# Avometer_v1_0.net
KiCad netlist of a schematic drawn in Altium Designer
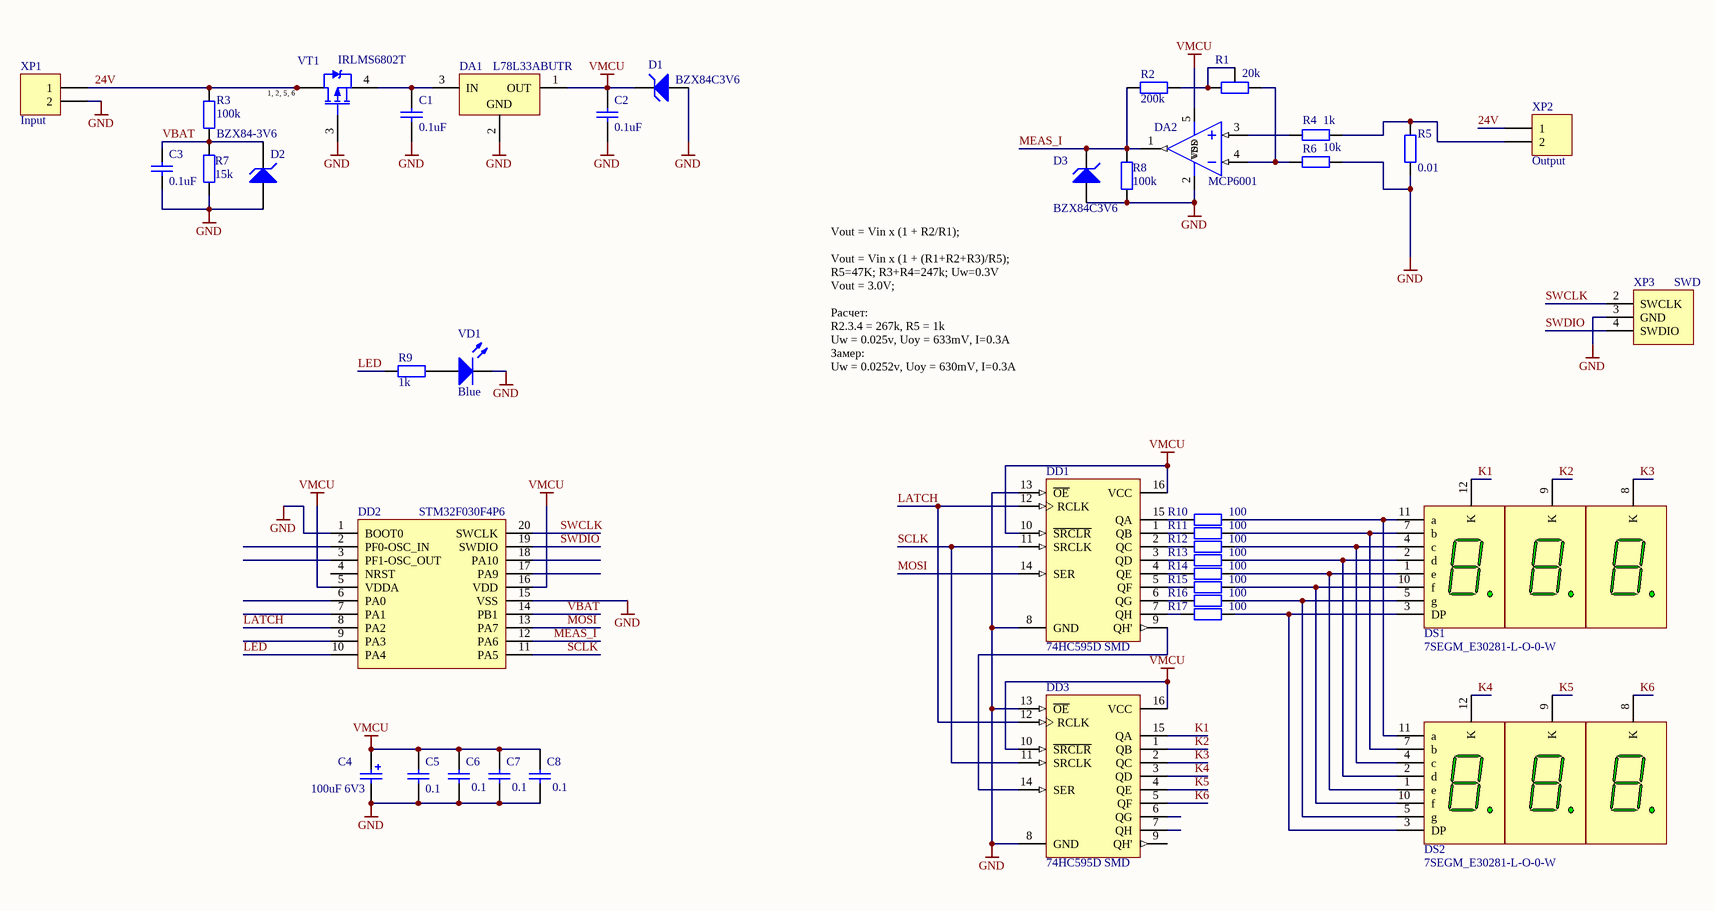
[diagram p0: Avometer v1.0.SchDoc]

(export (version "E")
  (design (tool "Eeschema 10.0.6"))
  (components
    (comp (ref "C1")
      (value "0.1uF")
      (footprint "CAP 0603_N")
      (description "Capacitor SMD")
      (libsource (lib "MyLibrary") (part "CAP_SMD"))
    )
    (comp (ref "C2")
      (value "0.1uF")
      (footprint "CAP 0603_N")
      (description "Capacitor SMD")
      (libsource (lib "MyLibrary") (part "CAP_SMD"))
    )
    (comp (ref "C3") (value "0.1uF") (footprint "CAP 0603_N") (libsource (lib "") (part "CAP_SMD_1")))
    (comp (ref "C4")
      (value "100uF 6V3")
      (footprint "CAP_TANT_B_TYPE_3528-21")
      (description "Capacitor SMD Tantalum")
      (libsource (lib "MyLibrary") (part "CAP_SMD_TANT"))
    )
    (comp (ref "C5")
      (value "0.1")
      (footprint "CAP 0603_N")
      (description "Capacitor SMD")
      (libsource (lib "MyLibrary") (part "CAP_SMD"))
    )
    (comp (ref "C6")
      (value "0.1")
      (footprint "CAP 0603_N")
      (description "Capacitor SMD")
      (libsource (lib "MyLibrary") (part "CAP_SMD"))
    )
    (comp (ref "C7")
      (value "0.1")
      (footprint "CAP 0603_N")
      (description "Capacitor SMD")
      (libsource (lib "MyLibrary") (part "CAP_SMD"))
    )
    (comp (ref "C8")
      (value "0.1")
      (footprint "CAP 0603_N")
      (description "Capacitor SMD")
      (libsource (lib "MyLibrary") (part "CAP_SMD"))
    )
    (comp (ref "D1")
      (value "BZX84C3V6")
      (footprint "SOT-23_L")
      (description "Zener Diode")
      (fields (field (name "PUBLISHER") "Altium Limited"))
      (libsource (lib "MyLibrary") (part "BZX84"))
    )
    (comp (ref "D2")
      (value "BZX84-3V6")
      (footprint "SOT-23_L")
      (description "Zener Diode")
      (fields (field (name "PUBLISHER") "Altium Limited"))
      (libsource (lib "") (part "BZX84_1"))
    )
    (comp (ref "D3")
      (value "BZX84C3V6")
      (footprint "SOT-23_L")
      (description "Zener Diode")
      (fields (field (name "PUBLISHER") "Altium Limited"))
      (libsource (lib "MyLibrary") (part "BZX84"))
    )
    (comp (ref "DA1")
      (value "L78L33ABUTR")
      (footprint "SOT-89")
      (description "Vin=30V Positive Voltage Regulator")
      (fields (field (name "PUBLISHER") "Altium Limited"))
      (libsource (lib "MyLibrary") (part "L78L33ABUTR"))
    )
    (comp (ref "DA2")
      (value "MCP6001")
      (footprint "SOT-23-5_L")
      (description "1 MHz, Low-Power Op Amp")
      (libsource (lib "MyLibrary") (part "MCP6001"))
    )
    (comp (ref "DD1")
      (value "74HC595D SMD")
      (footprint "SOIC-16_L")
      (description "8-Bit Shift Register with 3-State Output Registers")
      (fields (field (name "PUBLISHER") "Altium Limited"))
      (libsource (lib "MyLibrary") (part "74HC595D SMD"))
    )
    (comp (ref "DD2")
      (value "STM32F030F4P6")
      (footprint "TSSOP-20_N")
      (description "Cortex-M0 32-bit MCU, 16 KB Flash, 4 KB Internal RAM, 15 I/Os, 20-pin TSSOP, -40 to 85 degC")
      (libsource (lib "MyLibrary") (part "STM32F030F4P6"))
    )
    (comp (ref "DD3")
      (value "74HC595D SMD")
      (footprint "SOIC-16_L")
      (description "8-Bit Shift Register with 3-State Output Registers")
      (fields (field (name "PUBLISHER") "Altium Limited"))
      (libsource (lib "MyLibrary") (part "74HC595D SMD"))
    )
    (comp (ref "DS1")
      (value "7SEGM_E30281-L-O-0-W")
      (footprint "7SEGM_E30281-L-O-0-W GREEN")
      (description "7 mm Black Surface Green 7-Segment Display: CC, RH DP")
      (fields (field (name "PUBLISHER") "Altium Limited"))
      (libsource (lib "MyLibrary") (part "7SEGM_E30281-L-O-0-W"))
    )
    (comp (ref "DS2")
      (value "7SEGM_E30281-L-O-0-W")
      (footprint "7SEGM_E30281-L-O-0-W RED")
      (description "7 mm Black Surface Green 7-Segment Display: CC, RH DP")
      (fields (field (name "PUBLISHER") "Altium Limited"))
      (libsource (lib "MyLibrary") (part "7SEGM_E30281-L-O-0-W"))
    )
    (comp (ref "R1")
      (value "20k")
      (footprint "RES VAR 1")
      (description "Tapped Resistor")
      (fields (field (name "PUBLISHER") "Altium Limited"))
      (libsource (lib "MyLibrary") (part "RES_SMD_Tap"))
    )
    (comp (ref "R2") (value "200k") (footprint "RES 0603_N") (libsource (lib "") (part "Resistor_SMD_1")))
    (comp (ref "R3") (value "100k") (footprint "RES 0603_N") (libsource (lib "MyLibrary") (part "RES_SMD")))
    (comp (ref "R4") (value "1k") (footprint "RES 0603_N") (libsource (lib "") (part "Resistor_SMD_1")))
    (comp (ref "R5")
      (value "0.01")
      (footprint "RES 2512")
      (description "Resistor")
      (libsource (lib "MyLibrary") (part "RES_SMD"))
    )
    (comp (ref "R6") (value "10k") (footprint "RES 0603_N") (libsource (lib "") (part "Resistor_SMD_1")))
    (comp (ref "R7") (value "15k") (footprint "RES 0603_N") (libsource (lib "MyLibrary") (part "RES_SMD")))
    (comp (ref "R8")
      (value "100k")
      (footprint "RES 0603_N")
      (libsource (lib "MyLibrary") (part "Resistor_SMD"))
    )
    (comp (ref "R9") (value "1k") (footprint "RES 0603_N") (libsource (lib "") (part "RES_SMD_1")))
    (comp (ref "R10")
      (value "100")
      (footprint "RES 0603_N")
      (libsource (lib "MyLibrary") (part "Resistor_SMD"))
    )
    (comp (ref "R11")
      (value "100")
      (footprint "RES 0603_N")
      (libsource (lib "MyLibrary") (part "Resistor_SMD"))
    )
    (comp (ref "R12")
      (value "100")
      (footprint "RES 0603_N")
      (libsource (lib "MyLibrary") (part "Resistor_SMD"))
    )
    (comp (ref "R13")
      (value "100")
      (footprint "RES 0603_N")
      (libsource (lib "MyLibrary") (part "Resistor_SMD"))
    )
    (comp (ref "R14")
      (value "100")
      (footprint "RES 0603_N")
      (libsource (lib "MyLibrary") (part "Resistor_SMD"))
    )
    (comp (ref "R15")
      (value "100")
      (footprint "RES 0603_N")
      (libsource (lib "MyLibrary") (part "Resistor_SMD"))
    )
    (comp (ref "R16")
      (value "100")
      (footprint "RES 0603_N")
      (libsource (lib "MyLibrary") (part "Resistor_SMD"))
    )
    (comp (ref "R17")
      (value "100")
      (footprint "RES 0603_N")
      (libsource (lib "MyLibrary") (part "Resistor_SMD"))
    )
    (comp (ref "VD1")
      (value "Blue")
      (footprint "LED 0603 BLUE")
      (description "LED 0603")
      (fields (field (name "PUBLISHER") "Altium Limited"))
      (libsource (lib "MyLibrary") (part "LED_SMD_0603"))
    )
    (comp (ref "VT1")
      (value "IRLMS6802T")
      (footprint "SOT-23-6_L")
      (description "P-Channel MOSFET 20V 4.5A")
      (fields (field (name "PUBLISHER") "Altium Limited"))
      (libsource (lib "MyLibrary") (part "IRLMS6802T"))
    )
    (comp (ref "XP1")
      (value "Input")
      (footprint "CON_5.08MM_1X2")
      (description "Header, 2-Pin")
      (fields (field (name "PUBLISHER") "Altium Limited"))
      (libsource (lib "") (part "CON_5.08mm_1x2_1"))
    )
    (comp (ref "XP2")
      (value "Output")
      (footprint "CON_5.08MM_1X2")
      (description "Header, 2-Pin")
      (fields (field (name "PUBLISHER") "Altium Limited"))
      (libsource (lib "MyLibrary") (part "CON_5.08mm_1x2"))
    )
    (comp (ref "XP3")
      (value "SWD")
      (footprint "CON_1.27MM_1X3_SWD")
      (description "Header, 3-Pin")
      (fields (field (name "PUBLISHER") "Altium Limited"))
      (libsource (lib "MyLibrary") (part "CON_1.27mm_1x3_SWD"))
    )
  )
  (nets
    (net (code "1") (name "/24V") (class "Default")
      (node (ref "R3") (pin "2") (pinfunction "2_2") (pintype "passive"))
      (node (ref "VT1") (pin "1") (pinfunction "D_1") (pintype "passive"))
      (node (ref "VT1") (pin "2") (pinfunction "D_2") (pintype "passive"))
      (node (ref "VT1") (pin "5") (pinfunction "D_5") (pintype "passive"))
      (node (ref "VT1") (pin "6") (pinfunction "D_6") (pintype "passive"))
      (node (ref "XP1") (pin "1") (pinfunction "1_1") (pintype "passive"))
      (node (ref "XP2") (pin "1") (pinfunction "1_1") (pintype "passive"))
    )
    (net (code "2") (name "/K1") (class "Default")
      (node (ref "DD3") (pin "15") (pinfunction "QA_15") (pintype "tri_state"))
      (node (ref "DS1") (pin "12") (pinfunction "K_12") (pintype "passive"))
    )
    (net (code "3") (name "/K2") (class "Default")
      (node (ref "DD3") (pin "1") (pinfunction "QB_1") (pintype "tri_state"))
      (node (ref "DS1") (pin "9") (pinfunction "K_9") (pintype "passive"))
    )
    (net (code "4") (name "/K3") (class "Default")
      (node (ref "DD3") (pin "2") (pinfunction "QC_2") (pintype "tri_state"))
      (node (ref "DS1") (pin "8") (pinfunction "K_8") (pintype "passive"))
    )
    (net (code "5") (name "/K4") (class "Default")
      (node (ref "DD3") (pin "3") (pinfunction "QD_3") (pintype "tri_state"))
      (node (ref "DS2") (pin "12") (pinfunction "K_12") (pintype "passive"))
    )
    (net (code "6") (name "/K5") (class "Default")
      (node (ref "DD3") (pin "4") (pinfunction "QE_4") (pintype "tri_state"))
      (node (ref "DS2") (pin "9") (pinfunction "K_9") (pintype "passive"))
    )
    (net (code "7") (name "/K6") (class "Default")
      (node (ref "DD3") (pin "5") (pinfunction "QF_5") (pintype "tri_state"))
      (node (ref "DS2") (pin "8") (pinfunction "K_8") (pintype "passive"))
    )
    (net (code "8") (name "/LATCH") (class "Default")
      (node (ref "DD1") (pin "12") (pinfunction "RCLK_12") (pintype "input"))
      (node (ref "DD2") (pin "8") (pinfunction "PA2_8") (pintype "passive"))
      (node (ref "DD3") (pin "12") (pinfunction "RCLK_12") (pintype "input"))
    )
    (net (code "9") (name "/LED") (class "Default")
      (node (ref "DD2") (pin "10") (pinfunction "PA4_10") (pintype "passive"))
      (node (ref "R9") (pin "1") (pinfunction "1_1") (pintype "passive"))
    )
    (net (code "10") (name "/MEAS_I") (class "Default")
      (node (ref "D3") (pin "3") (pinfunction "K_3") (pintype "passive"))
      (node (ref "DA2") (pin "1") (pinfunction "VOUT_1") (pintype "output"))
      (node (ref "DD2") (pin "12") (pinfunction "PA6_12") (pintype "passive"))
      (node (ref "R2") (pin "2") (pinfunction "2_2") (pintype "passive"))
      (node (ref "R8") (pin "2") (pinfunction "2_2") (pintype "passive"))
    )
    (net (code "11") (name "/MOSI") (class "Default")
      (node (ref "DD1") (pin "14") (pinfunction "SER_14") (pintype "input"))
      (node (ref "DD2") (pin "13") (pinfunction "PA7_13") (pintype "passive"))
    )
    (net (code "12") (name "/SCLK") (class "Default")
      (node (ref "DD1") (pin "11") (pinfunction "SRCLK_11") (pintype "input"))
      (node (ref "DD2") (pin "11") (pinfunction "PA5_11") (pintype "passive"))
      (node (ref "DD3") (pin "11") (pinfunction "SRCLK_11") (pintype "input"))
    )
    (net (code "13") (name "/SWCLK") (class "Default")
      (node (ref "DD2") (pin "20") (pinfunction "SWCLK_20") (pintype "passive"))
      (node (ref "XP3") (pin "2") (pinfunction "SWCLK_2") (pintype "passive"))
    )
    (net (code "14") (name "/SWDIO") (class "Default")
      (node (ref "DD2") (pin "19") (pinfunction "SWDIO_19") (pintype "passive"))
      (node (ref "XP3") (pin "4") (pinfunction "SWDIO_4") (pintype "passive"))
    )
    (net (code "15") (name "/VBAT") (class "Default")
      (node (ref "C3") (pin "2") (pinfunction "2_2") (pintype "passive"))
      (node (ref "D2") (pin "3") (pinfunction "K_3") (pintype "passive"))
      (node (ref "DD2") (pin "14") (pinfunction "PB1_14") (pintype "passive"))
      (node (ref "R3") (pin "1") (pinfunction "1_1") (pintype "passive"))
      (node (ref "R7") (pin "2") (pinfunction "2_2") (pintype "passive"))
    )
    (net (code "16") (name "GND") (class "Default")
      (node (ref "C1") (pin "1") (pinfunction "1_1") (pintype "passive"))
      (node (ref "C2") (pin "1") (pinfunction "1_1") (pintype "passive"))
      (node (ref "C3") (pin "1") (pinfunction "1_1") (pintype "passive"))
      (node (ref "C4") (pin "2") (pinfunction "2_2") (pintype "passive"))
      (node (ref "C5") (pin "1") (pinfunction "1_1") (pintype "passive"))
      (node (ref "C6") (pin "2") (pinfunction "2_2") (pintype "passive"))
      (node (ref "C7") (pin "2") (pinfunction "2_2") (pintype "passive"))
      (node (ref "C8") (pin "2") (pinfunction "2_2") (pintype "passive"))
      (node (ref "D1") (pin "1") (pinfunction "A_1") (pintype "passive"))
      (node (ref "D2") (pin "1") (pinfunction "A_1") (pintype "passive"))
      (node (ref "D3") (pin "1") (pinfunction "A_1") (pintype "passive"))
      (node (ref "DA1") (pin "2") (pinfunction "GND_2") (pintype "power_in"))
      (node (ref "DA2") (pin "2") (pinfunction "VSS_2") (pintype "power_in"))
      (node (ref "DD1") (pin "13") (pinfunction "~{OE}_13") (pintype "input"))
      (node (ref "DD1") (pin "8") (pinfunction "GND_8") (pintype "power_in"))
      (node (ref "DD2") (pin "1") (pinfunction "BOOT0_1") (pintype "passive"))
      (node (ref "DD2") (pin "15") (pinfunction "VSS_15") (pintype "passive"))
      (node (ref "DD3") (pin "13") (pinfunction "~{OE}_13") (pintype "input"))
      (node (ref "DD3") (pin "8") (pinfunction "GND_8") (pintype "power_in"))
      (node (ref "R5") (pin "1") (pinfunction "1_1") (pintype "passive"))
      (node (ref "R6") (pin "1") (pinfunction "1_1") (pintype "passive"))
      (node (ref "R7") (pin "1") (pinfunction "1_1") (pintype "passive"))
      (node (ref "R8") (pin "1") (pinfunction "1_1") (pintype "passive"))
      (node (ref "VD1") (pin "2") (pinfunction "K_2") (pintype "passive"))
      (node (ref "VT1") (pin "3") (pinfunction "G_3") (pintype "passive"))
      (node (ref "XP1") (pin "2") (pinfunction "2_2") (pintype "passive"))
      (node (ref "XP3") (pin "3") (pinfunction "GND_3") (pintype "passive"))
    )
    (net (code "17") (name "Net-(DA1-IN)") (class "Default")
      (node (ref "C1") (pin "2") (pinfunction "2_2") (pintype "passive"))
      (node (ref "DA1") (pin "3") (pinfunction "IN_3") (pintype "power_in"))
      (node (ref "VT1") (pin "4") (pinfunction "S_4") (pintype "passive"))
    )
    (net (code "18") (name "Net-(DA2-VIN+)") (class "Default")
      (node (ref "DA2") (pin "3") (pinfunction "VIN+_3") (pintype "input"))
      (node (ref "R4") (pin "2") (pinfunction "2_2") (pintype "passive"))
    )
    (net (code "19") (name "Net-(DA2-VIN-)") (class "Default")
      (node (ref "DA2") (pin "4") (pinfunction "VIN-_4") (pintype "input"))
      (node (ref "R1") (pin "3") (pinfunction "B_3") (pintype "passive"))
      (node (ref "R6") (pin "2") (pinfunction "2_2") (pintype "passive"))
    )
    (net (code "20") (name "Net-(DD1-QA)") (class "Default")
      (node (ref "DD1") (pin "15") (pinfunction "QA_15") (pintype "tri_state"))
      (node (ref "R10") (pin "1") (pinfunction "1_1") (pintype "passive"))
    )
    (net (code "21") (name "Net-(DD1-QB)") (class "Default")
      (node (ref "DD1") (pin "1") (pinfunction "QB_1") (pintype "tri_state"))
      (node (ref "R11") (pin "1") (pinfunction "1_1") (pintype "passive"))
    )
    (net (code "22") (name "Net-(DD1-QC)") (class "Default")
      (node (ref "DD1") (pin "2") (pinfunction "QC_2") (pintype "tri_state"))
      (node (ref "R12") (pin "1") (pinfunction "1_1") (pintype "passive"))
    )
    (net (code "23") (name "Net-(DD1-QD)") (class "Default")
      (node (ref "DD1") (pin "3") (pinfunction "QD_3") (pintype "tri_state"))
      (node (ref "R13") (pin "1") (pinfunction "1_1") (pintype "passive"))
    )
    (net (code "24") (name "Net-(DD1-QE)") (class "Default")
      (node (ref "DD1") (pin "4") (pinfunction "QE_4") (pintype "tri_state"))
      (node (ref "R14") (pin "1") (pinfunction "1_1") (pintype "passive"))
    )
    (net (code "25") (name "Net-(DD1-QF)") (class "Default")
      (node (ref "DD1") (pin "5") (pinfunction "QF_5") (pintype "tri_state"))
      (node (ref "R15") (pin "1") (pinfunction "1_1") (pintype "passive"))
    )
    (net (code "26") (name "Net-(DD1-QG)") (class "Default")
      (node (ref "DD1") (pin "6") (pinfunction "QG_6") (pintype "tri_state"))
      (node (ref "R16") (pin "1") (pinfunction "1_1") (pintype "passive"))
    )
    (net (code "27") (name "Net-(DD1-QH')") (class "Default")
      (node (ref "DD1") (pin "9") (pinfunction "QH'_9") (pintype "output"))
      (node (ref "DD3") (pin "14") (pinfunction "SER_14") (pintype "input"))
    )
    (net (code "28") (name "Net-(DD1-QH)") (class "Default")
      (node (ref "DD1") (pin "7") (pinfunction "QH_7") (pintype "tri_state"))
      (node (ref "R17") (pin "1") (pinfunction "1_1") (pintype "passive"))
    )
    (net (code "29") (name "Net-(DS1-DP)") (class "Default")
      (node (ref "DS1") (pin "3") (pinfunction "DP_3") (pintype "passive"))
      (node (ref "DS2") (pin "3") (pinfunction "DP_3") (pintype "passive"))
      (node (ref "R17") (pin "2") (pinfunction "2_2") (pintype "passive"))
    )
    (net (code "30") (name "Net-(DS1-a)") (class "Default")
      (node (ref "DS1") (pin "11") (pinfunction "a_11") (pintype "passive"))
      (node (ref "DS2") (pin "11") (pinfunction "a_11") (pintype "passive"))
      (node (ref "R10") (pin "2") (pinfunction "2_2") (pintype "passive"))
    )
    (net (code "31") (name "Net-(DS1-b)") (class "Default")
      (node (ref "DS1") (pin "7") (pinfunction "b_7") (pintype "passive"))
      (node (ref "DS2") (pin "7") (pinfunction "b_7") (pintype "passive"))
      (node (ref "R11") (pin "2") (pinfunction "2_2") (pintype "passive"))
    )
    (net (code "32") (name "Net-(DS1-c)") (class "Default")
      (node (ref "DS1") (pin "4") (pinfunction "c_4") (pintype "passive"))
      (node (ref "DS2") (pin "4") (pinfunction "c_4") (pintype "passive"))
      (node (ref "R12") (pin "2") (pinfunction "2_2") (pintype "passive"))
    )
    (net (code "33") (name "Net-(DS1-d)") (class "Default")
      (node (ref "DS1") (pin "2") (pinfunction "d_2") (pintype "passive"))
      (node (ref "DS2") (pin "2") (pinfunction "d_2") (pintype "passive"))
      (node (ref "R13") (pin "2") (pinfunction "2_2") (pintype "passive"))
    )
    (net (code "34") (name "Net-(DS1-e)") (class "Default")
      (node (ref "DS1") (pin "1") (pinfunction "e_1") (pintype "passive"))
      (node (ref "DS2") (pin "1") (pinfunction "e_1") (pintype "passive"))
      (node (ref "R14") (pin "2") (pinfunction "2_2") (pintype "passive"))
    )
    (net (code "35") (name "Net-(DS1-f)") (class "Default")
      (node (ref "DS1") (pin "10") (pinfunction "f_10") (pintype "passive"))
      (node (ref "DS2") (pin "10") (pinfunction "f_10") (pintype "passive"))
      (node (ref "R15") (pin "2") (pinfunction "2_2") (pintype "passive"))
    )
    (net (code "36") (name "Net-(DS1-g)") (class "Default")
      (node (ref "DS1") (pin "5") (pinfunction "g_5") (pintype "passive"))
      (node (ref "DS2") (pin "5") (pinfunction "g_5") (pintype "passive"))
      (node (ref "R16") (pin "2") (pinfunction "2_2") (pintype "passive"))
    )
    (net (code "37") (name "Net-(R1-A)") (class "Default")
      (node (ref "R1") (pin "1") (pinfunction "A_1") (pintype "passive"))
      (node (ref "R1") (pin "2") (pinfunction "TAP_2") (pintype "passive"))
      (node (ref "R2") (pin "1") (pinfunction "1_1") (pintype "passive"))
    )
    (net (code "38") (name "Net-(R4-Pad1)") (class "Default")
      (node (ref "R4") (pin "1") (pinfunction "1_1") (pintype "passive"))
      (node (ref "R5") (pin "2") (pinfunction "2_2") (pintype "passive"))
      (node (ref "XP2") (pin "2") (pinfunction "2_2") (pintype "passive"))
    )
    (net (code "39") (name "Net-(VD1-A)") (class "Default")
      (node (ref "R9") (pin "2") (pinfunction "2_2") (pintype "passive"))
      (node (ref "VD1") (pin "1") (pinfunction "A_1") (pintype "passive"))
    )
    (net (code "40") (name "VMCU") (class "Default")
      (node (ref "C2") (pin "2") (pinfunction "2_2") (pintype "passive"))
      (node (ref "C4") (pin "1") (pinfunction "1_1") (pintype "passive"))
      (node (ref "C5") (pin "2") (pinfunction "2_2") (pintype "passive"))
      (node (ref "C6") (pin "1") (pinfunction "1_1") (pintype "passive"))
      (node (ref "C7") (pin "1") (pinfunction "1_1") (pintype "passive"))
      (node (ref "C8") (pin "1") (pinfunction "1_1") (pintype "passive"))
      (node (ref "D1") (pin "3") (pinfunction "K_3") (pintype "passive"))
      (node (ref "DA1") (pin "1") (pinfunction "OUT_1") (pintype "power_in"))
      (node (ref "DA2") (pin "5") (pinfunction "VDD_5") (pintype "power_in"))
      (node (ref "DD1") (pin "10") (pinfunction "~{SRCLR}_10") (pintype "input"))
      (node (ref "DD1") (pin "16") (pinfunction "VCC_16") (pintype "power_in"))
      (node (ref "DD2") (pin "16") (pinfunction "VDD_16") (pintype "passive"))
      (node (ref "DD2") (pin "5") (pinfunction "VDDA_5") (pintype "passive"))
      (node (ref "DD3") (pin "10") (pinfunction "~{SRCLR}_10") (pintype "input"))
      (node (ref "DD3") (pin "16") (pinfunction "VCC_16") (pintype "power_in"))
    )
    (net (code "41") (name "unconnected-(DD2-NRST-Pad4)") (class "Default")
      (node (ref "DD2") (pin "4") (pinfunction "NRST_4") (pintype "passive"))
    )
    (net (code "42") (name "unconnected-(DD2-PA0-Pad6)") (class "Default")
      (node (ref "DD2") (pin "6") (pinfunction "PA0_6") (pintype "passive"))
    )
    (net (code "43") (name "unconnected-(DD2-PA1-Pad7)") (class "Default")
      (node (ref "DD2") (pin "7") (pinfunction "PA1_7") (pintype "passive"))
    )
    (net (code "44") (name "unconnected-(DD2-PA3-Pad9)") (class "Default")
      (node (ref "DD2") (pin "9") (pinfunction "PA3_9") (pintype "passive"))
    )
    (net (code "45") (name "unconnected-(DD2-PA9-Pad17)") (class "Default")
      (node (ref "DD2") (pin "17") (pinfunction "PA9_17") (pintype "passive"))
    )
    (net (code "46") (name "unconnected-(DD2-PA10-Pad18)") (class "Default")
      (node (ref "DD2") (pin "18") (pinfunction "PA10_18") (pintype "passive"))
    )
    (net (code "47") (name "unconnected-(DD2-PF0-OSC_IN-Pad2)") (class "Default")
      (node (ref "DD2") (pin "2") (pinfunction "PF0-OSC_IN_2") (pintype "passive"))
    )
    (net (code "48") (name "unconnected-(DD2-PF1-OSC_OUT-Pad3)") (class "Default")
      (node (ref "DD2") (pin "3") (pinfunction "PF1-OSC_OUT_3") (pintype "passive"))
    )
    (net (code "49") (name "unconnected-(DD3-QG-Pad6)") (class "Default")
      (node (ref "DD3") (pin "6") (pinfunction "QG_6") (pintype "tri_state"))
    )
    (net (code "50") (name "unconnected-(DD3-QH'-Pad9)") (class "Default")
      (node (ref "DD3") (pin "9") (pinfunction "QH'_9") (pintype "output"))
    )
    (net (code "51") (name "unconnected-(DD3-QH-Pad7)") (class "Default")
      (node (ref "DD3") (pin "7") (pinfunction "QH_7") (pintype "tri_state"))
    )
  )
)
